# schematic.net
KiCad netlist of a schematic drawn in Altium Designer
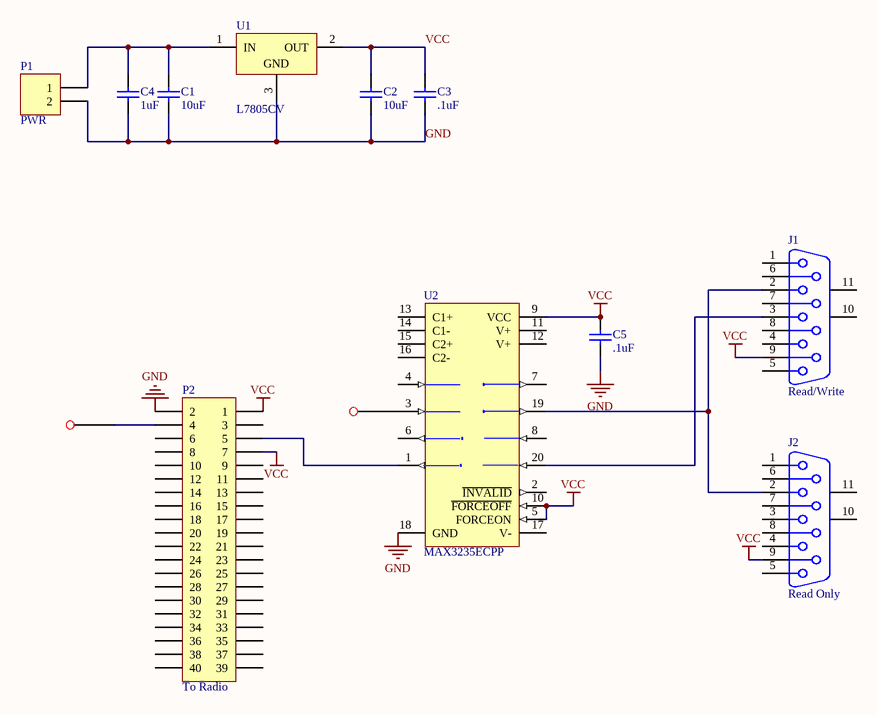
[diagram p0: schematic.SchDoc]

(export (version "E")
  (design (tool "Eeschema 10.0.6"))
  (components
    (comp (ref "C1")
      (value "10uF")
      (footprint "1206")
      (description "Capacitor")
      (fields (field (name "PUBLISHER") "Altium Limited"))
      (libsource (lib "Miscellaneous Devices") (part "Cap"))
    )
    (comp (ref "C2")
      (value "10uF")
      (footprint "1206")
      (description "Capacitor")
      (fields (field (name "PUBLISHER") "Altium Limited"))
      (libsource (lib "Miscellaneous Devices") (part "Cap"))
    )
    (comp (ref "C3")
      (value ".1uF")
      (footprint "1206")
      (description "Capacitor")
      (fields (field (name "PUBLISHER") "Altium Limited"))
      (libsource (lib "Miscellaneous Devices") (part "Cap"))
    )
    (comp (ref "C4")
      (value "1uF")
      (footprint "1206")
      (description "Capacitor")
      (fields (field (name "PUBLISHER") "Altium Limited"))
      (libsource (lib "Miscellaneous Devices") (part "Cap"))
    )
    (comp (ref "C5")
      (value ".1uF")
      (footprint "1206")
      (description "Capacitor")
      (fields (field (name "PUBLISHER") "Altium Limited"))
      (libsource (lib "Miscellaneous Devices") (part "Cap"))
    )
    (comp (ref "J1")
      (value "Read/Write")
      (footprint "DE-9")
      (description "Receptacle Assembly, 9 Position, Right Angle")
      (fields (field (name "PUBLISHER") "Altium Limited"))
      (libsource (lib "Miscellaneous Connectors") (part "D Connector 9"))
    )
    (comp (ref "J2")
      (value "Read Only")
      (footprint "DE-9")
      (description "Receptacle Assembly, 9 Position, Right Angle")
      (fields (field (name "PUBLISHER") "Altium Limited"))
      (libsource (lib "Miscellaneous Connectors") (part "D Connector 9"))
    )
    (comp (ref "P1")
      (value "PWR")
      (footprint "Screw Terminal - 2")
      (description "Header, 2-Pin")
      (fields (field (name "PUBLISHER") "Altium Limited"))
      (libsource (lib "Miscellaneous Connectors") (part "Header 2"))
    )
    (comp (ref "P2")
      (value "To Radio")
      (footprint "Header 2x20 2mm r&c pitch")
      (description "Header, 20-Pin, Dual row")
      (fields (field (name "PUBLISHER") "Altium Limited"))
      (libsource (lib "Miscellaneous Connectors") (part "Header 20X2"))
    )
    (comp (ref "P3")
      (value "~")
      (footprint "Solder Pad")
      (description "A pad to solder a wire connection to")
      (libsource (lib "schLib") (part "Solder Pad"))
    )
    (comp (ref "P4")
      (value "~")
      (footprint "Solder Pad")
      (description "A pad to solder a wire connection to")
      (libsource (lib "schLib") (part "Solder Pad"))
    )
    (comp (ref "U1")
      (value "L7805CV")
      (footprint "TO220ABN")
      (description "Positive Voltage Regulator")
      (fields (field (name "PUBLISHER") "Altium Limited"))
      (libsource (lib "ST Power Mgt Voltage Regulator") (part "L7805CV"))
    )
    (comp (ref "U2")
      (value "MAX3235ECPP")
      (footprint "PP20")
      (description "±15kV ESD-Protected, 1µA, 250kbps, 5V, Dual RS-232 Transceiver with Internal Capacitor")
      (fields (field (name "PUBLISHER") "Altium Limited"))
      (libsource (lib "Maxim Communication Transceiver") (part "MAX3235ECPP"))
    )
  )
  (nets
    (net (code "1") (name "GND") (class "Default")
      (node (ref "C1") (pin "1") (pinfunction "1_1") (pintype "passive"))
      (node (ref "C2") (pin "1") (pinfunction "1_1") (pintype "passive"))
      (node (ref "C3") (pin "1") (pinfunction "1_1") (pintype "passive"))
      (node (ref "C4") (pin "1") (pinfunction "1_1") (pintype "passive"))
      (node (ref "C5") (pin "1") (pinfunction "1_1") (pintype "passive"))
      (node (ref "P1") (pin "2") (pinfunction "2_2") (pintype "passive"))
      (node (ref "P2") (pin "2") (pinfunction "2_2") (pintype "passive"))
      (node (ref "U1") (pin "3") (pinfunction "GND_3") (pintype "power_in"))
      (node (ref "U2") (pin "18") (pinfunction "GND_18") (pintype "power_in"))
    )
    (net (code "2") (name "Net-(P2-Pad4)") (class "Default")
      (node (ref "P2") (pin "4") (pinfunction "4_4") (pintype "passive"))
      (node (ref "P3") (pin "1") (pinfunction "1_1") (pintype "passive"))
    )
    (net (code "3") (name "Net-(U1-IN)") (class "Default")
      (node (ref "C1") (pin "2") (pinfunction "2_2") (pintype "passive"))
      (node (ref "C4") (pin "2") (pinfunction "2_2") (pintype "passive"))
      (node (ref "P1") (pin "1") (pinfunction "1_1") (pintype "passive"))
      (node (ref "U1") (pin "1") (pinfunction "IN_1") (pintype "power_in"))
    )
    (net (code "4") (name "Net-(U2-R2IN)") (class "Default")
      (node (ref "J1") (pin "3") (pinfunction "3_3") (pintype "passive"))
      (node (ref "U2") (pin "20") (pinfunction "R2IN_20") (pintype "input"))
    )
    (net (code "5") (name "Net-(U2-R2OUT)") (class "Default")
      (node (ref "P2") (pin "5") (pinfunction "5_5") (pintype "passive"))
      (node (ref "U2") (pin "1") (pinfunction "R2OUT_1") (pintype "output"))
    )
    (net (code "6") (name "Net-(U2-T2IN)") (class "Default")
      (node (ref "P4") (pin "1") (pinfunction "1_1") (pintype "passive"))
      (node (ref "U2") (pin "3") (pinfunction "T2IN_3") (pintype "input"))
    )
    (net (code "7") (name "Net-(U2-T2OUT)") (class "Default")
      (node (ref "J1") (pin "2") (pinfunction "2_2") (pintype "passive"))
      (node (ref "J2") (pin "2") (pinfunction "2_2") (pintype "passive"))
      (node (ref "U2") (pin "19") (pinfunction "T2OUT_19") (pintype "output"))
    )
    (net (code "8") (name "VCC") (class "Default")
      (node (ref "C2") (pin "2") (pinfunction "2_2") (pintype "passive"))
      (node (ref "C3") (pin "2") (pinfunction "2_2") (pintype "passive"))
      (node (ref "C5") (pin "2") (pinfunction "2_2") (pintype "passive"))
      (node (ref "J1") (pin "9") (pinfunction "9_9") (pintype "passive"))
      (node (ref "J2") (pin "9") (pinfunction "9_9") (pintype "passive"))
      (node (ref "P2") (pin "1") (pinfunction "1_1") (pintype "passive"))
      (node (ref "P2") (pin "7") (pinfunction "7_7") (pintype "passive"))
      (node (ref "U1") (pin "2") (pinfunction "OUT_2") (pintype "power_in"))
      (node (ref "U2") (pin "10") (pinfunction "~{FORCEOFF}_10") (pintype "input"))
      (node (ref "U2") (pin "5") (pinfunction "FORCEON_5") (pintype "input"))
      (node (ref "U2") (pin "9") (pinfunction "VCC_9") (pintype "power_in"))
    )
    (net (code "9") (name "unconnected-(J1-MH1-Pad10)") (class "Default")
      (node (ref "J1") (pin "10") (pinfunction "MH1_10") (pintype "passive"))
    )
    (net (code "10") (name "unconnected-(J1-MH2-Pad11)") (class "Default")
      (node (ref "J1") (pin "11") (pinfunction "MH2_11") (pintype "passive"))
    )
    (net (code "11") (name "unconnected-(J1-Pad1)") (class "Default")
      (node (ref "J1") (pin "1") (pinfunction "1_1") (pintype "passive"))
    )
    (net (code "12") (name "unconnected-(J1-Pad4)") (class "Default")
      (node (ref "J1") (pin "4") (pinfunction "4_4") (pintype "passive"))
    )
    (net (code "13") (name "unconnected-(J1-Pad5)") (class "Default")
      (node (ref "J1") (pin "5") (pinfunction "5_5") (pintype "passive"))
    )
    (net (code "14") (name "unconnected-(J1-Pad6)") (class "Default")
      (node (ref "J1") (pin "6") (pinfunction "6_6") (pintype "passive"))
    )
    (net (code "15") (name "unconnected-(J1-Pad7)") (class "Default")
      (node (ref "J1") (pin "7") (pinfunction "7_7") (pintype "passive"))
    )
    (net (code "16") (name "unconnected-(J1-Pad8)") (class "Default")
      (node (ref "J1") (pin "8") (pinfunction "8_8") (pintype "passive"))
    )
    (net (code "17") (name "unconnected-(J2-MH1-Pad10)") (class "Default")
      (node (ref "J2") (pin "10") (pinfunction "MH1_10") (pintype "passive"))
    )
    (net (code "18") (name "unconnected-(J2-MH2-Pad11)") (class "Default")
      (node (ref "J2") (pin "11") (pinfunction "MH2_11") (pintype "passive"))
    )
    (net (code "19") (name "unconnected-(J2-Pad1)") (class "Default")
      (node (ref "J2") (pin "1") (pinfunction "1_1") (pintype "passive"))
    )
    (net (code "20") (name "unconnected-(J2-Pad3)") (class "Default")
      (node (ref "J2") (pin "3") (pinfunction "3_3") (pintype "passive"))
    )
    (net (code "21") (name "unconnected-(J2-Pad4)") (class "Default")
      (node (ref "J2") (pin "4") (pinfunction "4_4") (pintype "passive"))
    )
    (net (code "22") (name "unconnected-(J2-Pad5)") (class "Default")
      (node (ref "J2") (pin "5") (pinfunction "5_5") (pintype "passive"))
    )
    (net (code "23") (name "unconnected-(J2-Pad6)") (class "Default")
      (node (ref "J2") (pin "6") (pinfunction "6_6") (pintype "passive"))
    )
    (net (code "24") (name "unconnected-(J2-Pad7)") (class "Default")
      (node (ref "J2") (pin "7") (pinfunction "7_7") (pintype "passive"))
    )
    (net (code "25") (name "unconnected-(J2-Pad8)") (class "Default")
      (node (ref "J2") (pin "8") (pinfunction "8_8") (pintype "passive"))
    )
    (net (code "26") (name "unconnected-(P2-Pad3)") (class "Default")
      (node (ref "P2") (pin "3") (pinfunction "3_3") (pintype "passive"))
    )
    (net (code "27") (name "unconnected-(P2-Pad6)") (class "Default")
      (node (ref "P2") (pin "6") (pinfunction "6_6") (pintype "passive"))
    )
    (net (code "28") (name "unconnected-(P2-Pad8)") (class "Default")
      (node (ref "P2") (pin "8") (pinfunction "8_8") (pintype "passive"))
    )
    (net (code "29") (name "unconnected-(P2-Pad9)") (class "Default")
      (node (ref "P2") (pin "9") (pinfunction "9_9") (pintype "passive"))
    )
    (net (code "30") (name "unconnected-(P2-Pad10)") (class "Default")
      (node (ref "P2") (pin "10") (pinfunction "10_10") (pintype "passive"))
    )
    (net (code "31") (name "unconnected-(P2-Pad11)") (class "Default")
      (node (ref "P2") (pin "11") (pinfunction "11_11") (pintype "passive"))
    )
    (net (code "32") (name "unconnected-(P2-Pad12)") (class "Default")
      (node (ref "P2") (pin "12") (pinfunction "12_12") (pintype "passive"))
    )
    (net (code "33") (name "unconnected-(P2-Pad13)") (class "Default")
      (node (ref "P2") (pin "13") (pinfunction "13_13") (pintype "passive"))
    )
    (net (code "34") (name "unconnected-(P2-Pad14)") (class "Default")
      (node (ref "P2") (pin "14") (pinfunction "14_14") (pintype "passive"))
    )
    (net (code "35") (name "unconnected-(P2-Pad15)") (class "Default")
      (node (ref "P2") (pin "15") (pinfunction "15_15") (pintype "passive"))
    )
    (net (code "36") (name "unconnected-(P2-Pad16)") (class "Default")
      (node (ref "P2") (pin "16") (pinfunction "16_16") (pintype "passive"))
    )
    (net (code "37") (name "unconnected-(P2-Pad17)") (class "Default")
      (node (ref "P2") (pin "17") (pinfunction "17_17") (pintype "passive"))
    )
    (net (code "38") (name "unconnected-(P2-Pad18)") (class "Default")
      (node (ref "P2") (pin "18") (pinfunction "18_18") (pintype "passive"))
    )
    (net (code "39") (name "unconnected-(P2-Pad19)") (class "Default")
      (node (ref "P2") (pin "19") (pinfunction "19_19") (pintype "passive"))
    )
    (net (code "40") (name "unconnected-(P2-Pad20)") (class "Default")
      (node (ref "P2") (pin "20") (pinfunction "20_20") (pintype "passive"))
    )
    (net (code "41") (name "unconnected-(P2-Pad21)") (class "Default")
      (node (ref "P2") (pin "21") (pinfunction "21_21") (pintype "passive"))
    )
    (net (code "42") (name "unconnected-(P2-Pad22)") (class "Default")
      (node (ref "P2") (pin "22") (pinfunction "22_22") (pintype "passive"))
    )
    (net (code "43") (name "unconnected-(P2-Pad23)") (class "Default")
      (node (ref "P2") (pin "23") (pinfunction "23_23") (pintype "passive"))
    )
    (net (code "44") (name "unconnected-(P2-Pad24)") (class "Default")
      (node (ref "P2") (pin "24") (pinfunction "24_24") (pintype "passive"))
    )
    (net (code "45") (name "unconnected-(P2-Pad25)") (class "Default")
      (node (ref "P2") (pin "25") (pinfunction "25_25") (pintype "passive"))
    )
    (net (code "46") (name "unconnected-(P2-Pad26)") (class "Default")
      (node (ref "P2") (pin "26") (pinfunction "26_26") (pintype "passive"))
    )
    (net (code "47") (name "unconnected-(P2-Pad27)") (class "Default")
      (node (ref "P2") (pin "27") (pinfunction "27_27") (pintype "passive"))
    )
    (net (code "48") (name "unconnected-(P2-Pad28)") (class "Default")
      (node (ref "P2") (pin "28") (pinfunction "28_28") (pintype "passive"))
    )
    (net (code "49") (name "unconnected-(P2-Pad29)") (class "Default")
      (node (ref "P2") (pin "29") (pinfunction "29_29") (pintype "passive"))
    )
    (net (code "50") (name "unconnected-(P2-Pad30)") (class "Default")
      (node (ref "P2") (pin "30") (pinfunction "30_30") (pintype "passive"))
    )
    (net (code "51") (name "unconnected-(P2-Pad31)") (class "Default")
      (node (ref "P2") (pin "31") (pinfunction "31_31") (pintype "passive"))
    )
    (net (code "52") (name "unconnected-(P2-Pad32)") (class "Default")
      (node (ref "P2") (pin "32") (pinfunction "32_32") (pintype "passive"))
    )
    (net (code "53") (name "unconnected-(P2-Pad33)") (class "Default")
      (node (ref "P2") (pin "33") (pinfunction "33_33") (pintype "passive"))
    )
    (net (code "54") (name "unconnected-(P2-Pad34)") (class "Default")
      (node (ref "P2") (pin "34") (pinfunction "34_34") (pintype "passive"))
    )
    (net (code "55") (name "unconnected-(P2-Pad35)") (class "Default")
      (node (ref "P2") (pin "35") (pinfunction "35_35") (pintype "passive"))
    )
    (net (code "56") (name "unconnected-(P2-Pad36)") (class "Default")
      (node (ref "P2") (pin "36") (pinfunction "36_36") (pintype "passive"))
    )
    (net (code "57") (name "unconnected-(P2-Pad37)") (class "Default")
      (node (ref "P2") (pin "37") (pinfunction "37_37") (pintype "passive"))
    )
    (net (code "58") (name "unconnected-(P2-Pad38)") (class "Default")
      (node (ref "P2") (pin "38") (pinfunction "38_38") (pintype "passive"))
    )
    (net (code "59") (name "unconnected-(P2-Pad39)") (class "Default")
      (node (ref "P2") (pin "39") (pinfunction "39_39") (pintype "passive"))
    )
    (net (code "60") (name "unconnected-(P2-Pad40)") (class "Default")
      (node (ref "P2") (pin "40") (pinfunction "40_40") (pintype "passive"))
    )
    (net (code "61") (name "unconnected-(U2-C1+-Pad13)") (class "Default")
      (node (ref "U2") (pin "13") (pinfunction "C1+_13") (pintype "passive"))
    )
    (net (code "62") (name "unconnected-(U2-C1--Pad14)") (class "Default")
      (node (ref "U2") (pin "14") (pinfunction "C1-_14") (pintype "passive"))
    )
    (net (code "63") (name "unconnected-(U2-C2+-Pad15)") (class "Default")
      (node (ref "U2") (pin "15") (pinfunction "C2+_15") (pintype "passive"))
    )
    (net (code "64") (name "unconnected-(U2-C2--Pad16)") (class "Default")
      (node (ref "U2") (pin "16") (pinfunction "C2-_16") (pintype "passive"))
    )
    (net (code "65") (name "unconnected-(U2-R1IN-Pad8)") (class "Default")
      (node (ref "U2") (pin "8") (pinfunction "R1IN_8") (pintype "input"))
    )
    (net (code "66") (name "unconnected-(U2-R1OUT-Pad6)") (class "Default")
      (node (ref "U2") (pin "6") (pinfunction "R1OUT_6") (pintype "output"))
    )
    (net (code "67") (name "unconnected-(U2-T1IN-Pad4)") (class "Default")
      (node (ref "U2") (pin "4") (pinfunction "T1IN_4") (pintype "input"))
    )
    (net (code "68") (name "unconnected-(U2-T1OUT-Pad7)") (class "Default")
      (node (ref "U2") (pin "7") (pinfunction "T1OUT_7") (pintype "output"))
    )
    (net (code "69") (name "unconnected-(U2-V+-Pad11)") (class "Default")
      (node (ref "U2") (pin "11") (pinfunction "V+_11") (pintype "power_in"))
    )
    (net (code "70") (name "unconnected-(U2-V+-Pad12)") (class "Default")
      (node (ref "U2") (pin "12") (pinfunction "V+_12") (pintype "power_in"))
    )
    (net (code "71") (name "unconnected-(U2-V--Pad17)") (class "Default")
      (node (ref "U2") (pin "17") (pinfunction "V-_17") (pintype "power_in"))
    )
    (net (code "72") (name "unconnected-(U2-~{INVALID}-Pad2)") (class "Default")
      (node (ref "U2") (pin "2") (pinfunction "~{INVALID}_2") (pintype "output"))
    )
  )
)
